# y_carriage_board.net
KiCad netlist of a schematic drawn in EAGLE
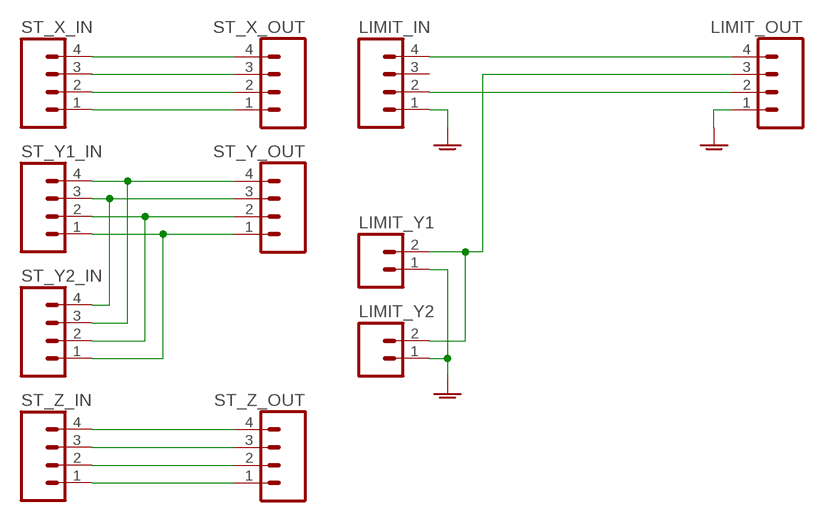
[diagram p0: schematic, sheet 1]

(export (version "E")
  (design (tool "Eeschema 10.0.6"))
  (components
    (comp (ref "LIMIT_IN")
      (value "M04POLAR")
      (footprint "eagle-import:MOLEX-1X4")
      (libsource (lib "eagle-import") (part "M04POLAR"))
    )
    (comp (ref "LIMIT_OUT")
      (value "M04POLAR")
      (footprint "eagle-import:MOLEX-1X4")
      (libsource (lib "eagle-import") (part "M04POLAR"))
    )
    (comp (ref "LIMIT_Y1")
      (value "M02POLAR")
      (footprint "eagle-import:MOLEX-1X2")
      (libsource (lib "eagle-import") (part "M02POLAR"))
    )
    (comp (ref "LIMIT_Y2")
      (value "M02POLAR")
      (footprint "eagle-import:MOLEX-1X2")
      (libsource (lib "eagle-import") (part "M02POLAR"))
    )
    (comp (ref "ST_X_IN")
      (value "M04POLAR")
      (footprint "eagle-import:MOLEX-1X4")
      (libsource (lib "eagle-import") (part "M04POLAR"))
    )
    (comp (ref "ST_X_OUT")
      (value "M04POLAR")
      (footprint "eagle-import:MOLEX-1X4")
      (libsource (lib "eagle-import") (part "M04POLAR"))
    )
    (comp (ref "ST_Y1_IN")
      (value "M04POLAR")
      (footprint "eagle-import:MOLEX-1X4")
      (libsource (lib "eagle-import") (part "M04POLAR"))
    )
    (comp (ref "ST_Y2_IN")
      (value "M04POLAR")
      (footprint "eagle-import:MOLEX-1X4")
      (libsource (lib "eagle-import") (part "M04POLAR"))
    )
    (comp (ref "ST_Y_OUT")
      (value "M04POLAR")
      (footprint "eagle-import:MOLEX-1X4")
      (libsource (lib "eagle-import") (part "M04POLAR"))
    )
    (comp (ref "ST_Z_IN")
      (value "M04POLAR")
      (footprint "eagle-import:MOLEX-1X4")
      (libsource (lib "eagle-import") (part "M04POLAR"))
    )
    (comp (ref "ST_Z_OUT")
      (value "M04POLAR")
      (footprint "eagle-import:MOLEX-1X4")
      (libsource (lib "eagle-import") (part "M04POLAR"))
    )
  )
  (nets
    (net (code "1") (name "GNDA") (class "Default")
      (node (ref "LIMIT_IN") (pin "1") (pinfunction "1_1") (pintype "passive"))
      (node (ref "LIMIT_OUT") (pin "1") (pinfunction "1_1") (pintype "passive"))
      (node (ref "LIMIT_Y1") (pin "1") (pinfunction "1_1") (pintype "passive"))
      (node (ref "LIMIT_Y2") (pin "1") (pinfunction "1_1") (pintype "passive"))
    )
    (net (code "2") (name "Net-(LIMIT_IN-Pad2)") (class "Default")
      (node (ref "LIMIT_IN") (pin "2") (pinfunction "2_2") (pintype "passive"))
      (node (ref "LIMIT_OUT") (pin "2") (pinfunction "2_2") (pintype "passive"))
    )
    (net (code "3") (name "Net-(LIMIT_IN-Pad4)") (class "Default")
      (node (ref "LIMIT_IN") (pin "4") (pinfunction "4_4") (pintype "passive"))
      (node (ref "LIMIT_OUT") (pin "4") (pinfunction "4_4") (pintype "passive"))
    )
    (net (code "4") (name "Net-(LIMIT_OUT-Pad3)") (class "Default")
      (node (ref "LIMIT_OUT") (pin "3") (pinfunction "3_3") (pintype "passive"))
      (node (ref "LIMIT_Y1") (pin "2") (pinfunction "2_2") (pintype "passive"))
      (node (ref "LIMIT_Y2") (pin "2") (pinfunction "2_2") (pintype "passive"))
    )
    (net (code "5") (name "Net-(ST_X_IN-Pad1)") (class "Default")
      (node (ref "ST_X_IN") (pin "1") (pinfunction "1_1") (pintype "passive"))
      (node (ref "ST_X_OUT") (pin "1") (pinfunction "1_1") (pintype "passive"))
    )
    (net (code "6") (name "Net-(ST_X_IN-Pad2)") (class "Default")
      (node (ref "ST_X_IN") (pin "2") (pinfunction "2_2") (pintype "passive"))
      (node (ref "ST_X_OUT") (pin "2") (pinfunction "2_2") (pintype "passive"))
    )
    (net (code "7") (name "Net-(ST_X_IN-Pad3)") (class "Default")
      (node (ref "ST_X_IN") (pin "3") (pinfunction "3_3") (pintype "passive"))
      (node (ref "ST_X_OUT") (pin "3") (pinfunction "3_3") (pintype "passive"))
    )
    (net (code "8") (name "Net-(ST_X_IN-Pad4)") (class "Default")
      (node (ref "ST_X_IN") (pin "4") (pinfunction "4_4") (pintype "passive"))
      (node (ref "ST_X_OUT") (pin "4") (pinfunction "4_4") (pintype "passive"))
    )
    (net (code "9") (name "Net-(ST_Y1_IN-Pad1)") (class "Default")
      (node (ref "ST_Y1_IN") (pin "1") (pinfunction "1_1") (pintype "passive"))
      (node (ref "ST_Y2_IN") (pin "1") (pinfunction "1_1") (pintype "passive"))
      (node (ref "ST_Y_OUT") (pin "1") (pinfunction "1_1") (pintype "passive"))
    )
    (net (code "10") (name "Net-(ST_Y1_IN-Pad2)") (class "Default")
      (node (ref "ST_Y1_IN") (pin "2") (pinfunction "2_2") (pintype "passive"))
      (node (ref "ST_Y2_IN") (pin "2") (pinfunction "2_2") (pintype "passive"))
      (node (ref "ST_Y_OUT") (pin "2") (pinfunction "2_2") (pintype "passive"))
    )
    (net (code "11") (name "Net-(ST_Y1_IN-Pad3)") (class "Default")
      (node (ref "ST_Y1_IN") (pin "3") (pinfunction "3_3") (pintype "passive"))
      (node (ref "ST_Y2_IN") (pin "4") (pinfunction "4_4") (pintype "passive"))
      (node (ref "ST_Y_OUT") (pin "3") (pinfunction "3_3") (pintype "passive"))
    )
    (net (code "12") (name "Net-(ST_Y1_IN-Pad4)") (class "Default")
      (node (ref "ST_Y1_IN") (pin "4") (pinfunction "4_4") (pintype "passive"))
      (node (ref "ST_Y2_IN") (pin "3") (pinfunction "3_3") (pintype "passive"))
      (node (ref "ST_Y_OUT") (pin "4") (pinfunction "4_4") (pintype "passive"))
    )
    (net (code "13") (name "Net-(ST_Z_IN-Pad1)") (class "Default")
      (node (ref "ST_Z_IN") (pin "1") (pinfunction "1_1") (pintype "passive"))
      (node (ref "ST_Z_OUT") (pin "1") (pinfunction "1_1") (pintype "passive"))
    )
    (net (code "14") (name "Net-(ST_Z_IN-Pad2)") (class "Default")
      (node (ref "ST_Z_IN") (pin "2") (pinfunction "2_2") (pintype "passive"))
      (node (ref "ST_Z_OUT") (pin "2") (pinfunction "2_2") (pintype "passive"))
    )
    (net (code "15") (name "Net-(ST_Z_IN-Pad3)") (class "Default")
      (node (ref "ST_Z_IN") (pin "3") (pinfunction "3_3") (pintype "passive"))
      (node (ref "ST_Z_OUT") (pin "3") (pinfunction "3_3") (pintype "passive"))
    )
    (net (code "16") (name "Net-(ST_Z_IN-Pad4)") (class "Default")
      (node (ref "ST_Z_IN") (pin "4") (pinfunction "4_4") (pintype "passive"))
      (node (ref "ST_Z_OUT") (pin "4") (pinfunction "4_4") (pintype "passive"))
    )
    (net (code "17") (name "unconnected-(LIMIT_IN-Pad3)") (class "Default")
      (node (ref "LIMIT_IN") (pin "3") (pinfunction "3_3") (pintype "passive"))
    )
  )
)
